# CAN-Bus_Shield.net
KiCad netlist of a schematic drawn in EAGLE
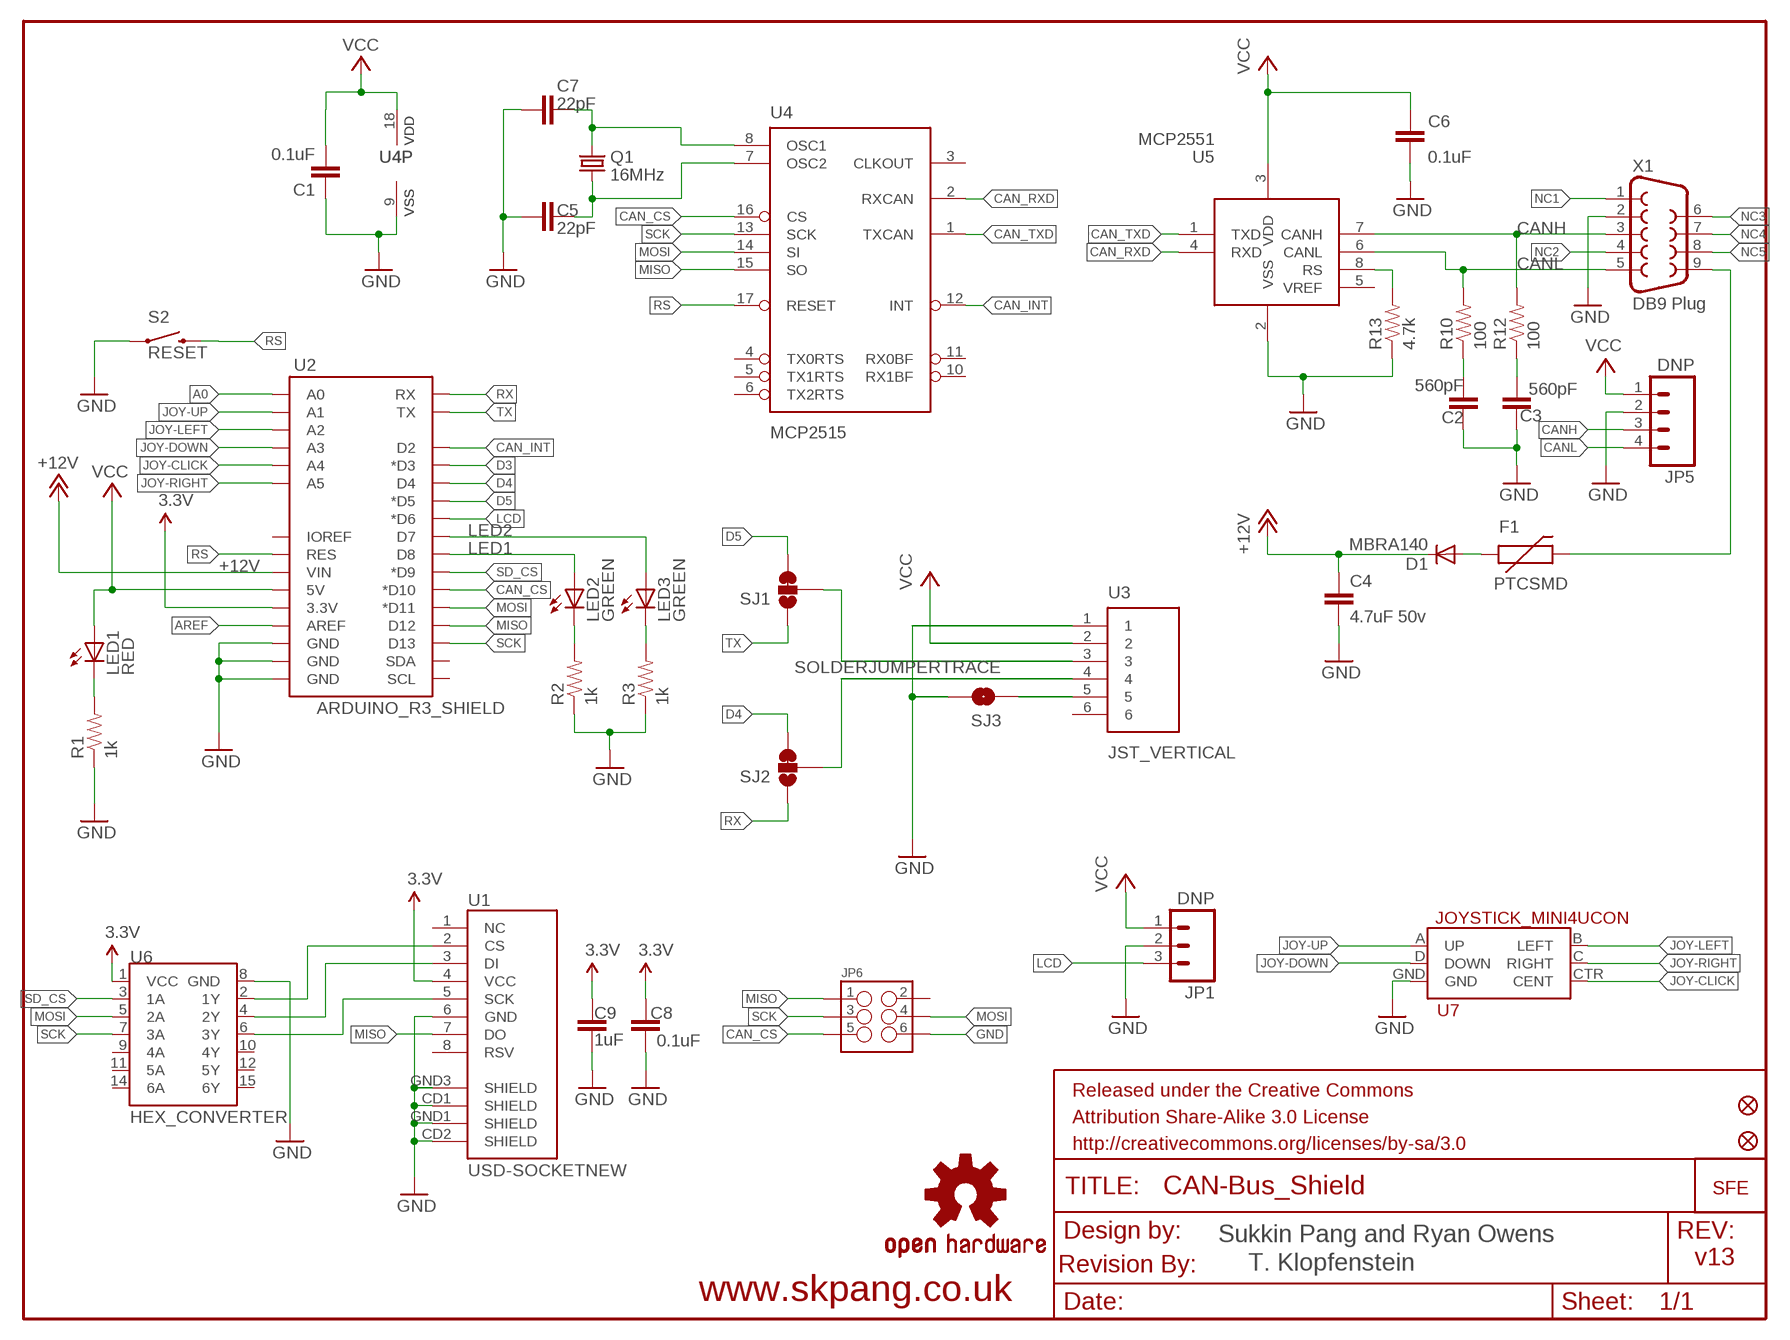
[diagram p0: schematic, sheet 1]

(export (version "E")
  (design (tool "Eeschema 10.0.6"))
  (components
    (comp (ref "C1")
      (value "0.1uF")
      (footprint "eagle-import:0603-CAP")
      (libsource (lib "eagle-import") (part "CAP0603-CAP"))
    )
    (comp (ref "C2")
      (value "560pF")
      (footprint "eagle-import:0603-CAP")
      (libsource (lib "eagle-import") (part "CAP0603-CAP"))
    )
    (comp (ref "C3")
      (value "560pF")
      (footprint "eagle-import:0603-CAP")
      (libsource (lib "eagle-import") (part "CAP0603-CAP"))
    )
    (comp (ref "C4")
      (value "4.7uF 50v")
      (footprint "eagle-import:0603-CAP")
      (libsource (lib "eagle-import") (part "CAP0603-CAP"))
    )
    (comp (ref "C5")
      (value "22pF")
      (footprint "eagle-import:0603-CAP")
      (libsource (lib "eagle-import") (part "CAP0603-CAP"))
    )
    (comp (ref "C6")
      (value "0.1uF")
      (footprint "eagle-import:0603-CAP")
      (libsource (lib "eagle-import") (part "CAP0603-CAP"))
    )
    (comp (ref "C7")
      (value "22pF")
      (footprint "eagle-import:0603-CAP")
      (libsource (lib "eagle-import") (part "CAP0603-CAP"))
    )
    (comp (ref "C8")
      (value "0.1uF")
      (footprint "eagle-import:0603-CAP")
      (libsource (lib "eagle-import") (part "CAP0603-CAP"))
    )
    (comp (ref "C9")
      (value "1uF")
      (footprint "eagle-import:0603-CAP")
      (libsource (lib "eagle-import") (part "CAP0603-CAP"))
    )
    (comp (ref "D1")
      (value "MBRA140")
      (footprint "eagle-import:SMA-DIODE")
      (libsource (lib "eagle-import") (part "DIODESMA"))
    )
    (comp (ref "F1")
      (value "PTCSMD")
      (footprint "eagle-import:PTC-1206")
      (libsource (lib "eagle-import") (part "PTCSMD"))
    )
    (comp (ref "FRAME1")
      (value "FRAME-LETTER")
      (footprint "eagle-import:CREATIVE_COMMONS")
      (libsource (lib "eagle-import") (part "FRAME-LETTER"))
    )
    (comp (ref "JP1")
      (value "DNP")
      (footprint "eagle-import:MOLEX-1X3_LOCK")
      (libsource (lib "eagle-import") (part "M03POLAR_LOCK"))
    )
    (comp (ref "JP2")
      (value "FIDUCIAL1X2")
      (footprint "eagle-import:FIDUCIAL-1X2")
      (libsource (lib "eagle-import") (part "FIDUCIAL1X2"))
    )
    (comp (ref "JP3")
      (value "FIDUCIAL1X2")
      (footprint "eagle-import:FIDUCIAL-1X2")
      (libsource (lib "eagle-import") (part "FIDUCIAL1X2"))
    )
    (comp (ref "JP4")
      (value "LOGO-SFENEW")
      (footprint "eagle-import:SFE-NEW-WEBLOGO")
      (libsource (lib "eagle-import") (part "LOGO-SFENEW"))
    )
    (comp (ref "JP5")
      (value "DNP")
      (footprint "eagle-import:1X04")
      (libsource (lib "eagle-import") (part "M04PTH"))
    )
    (comp (ref "JP6")
      (value "M03X2NO_SILK")
      (footprint "eagle-import:2X3-NS")
      (libsource (lib "eagle-import") (part "M03X2NO_SILK"))
    )
    (comp (ref "LED1")
      (value "RED")
      (footprint "eagle-import:LED-0603")
      (libsource (lib "eagle-import") (part "LED0603"))
    )
    (comp (ref "LED2")
      (value "GREEN")
      (footprint "eagle-import:LED-0603")
      (libsource (lib "eagle-import") (part "LED0603"))
    )
    (comp (ref "LED3")
      (value "GREEN")
      (footprint "eagle-import:LED-0603")
      (libsource (lib "eagle-import") (part "LED0603"))
    )
    (comp (ref "LOGO1")
      (value "OSHW-LOGOM")
      (footprint "eagle-import:OSHW-LOGO-M")
      (libsource (lib "eagle-import") (part "OSHW-LOGOM"))
    )
    (comp (ref "Q1")
      (value "16MHz")
      (footprint "eagle-import:CRYSTAL-SMD-5X3")
      (libsource (lib "eagle-import") (part "CRYSTAL5X3"))
    )
    (comp (ref "R1")
      (value "1k")
      (footprint "eagle-import:0603-RES")
      (libsource (lib "eagle-import") (part "RESISTOR0603-RES"))
    )
    (comp (ref "R2")
      (value "1k")
      (footprint "eagle-import:0603-RES")
      (libsource (lib "eagle-import") (part "RESISTOR0603-RES"))
    )
    (comp (ref "R3")
      (value "1k")
      (footprint "eagle-import:0603-RES")
      (libsource (lib "eagle-import") (part "RESISTOR0603-RES"))
    )
    (comp (ref "R10")
      (value "100")
      (footprint "eagle-import:0603-RES")
      (libsource (lib "eagle-import") (part "RESISTOR0603-RES"))
    )
    (comp (ref "R12")
      (value "100")
      (footprint "eagle-import:0603-RES")
      (libsource (lib "eagle-import") (part "RESISTOR0603-RES"))
    )
    (comp (ref "R13")
      (value "4.7k")
      (footprint "eagle-import:0603-RES")
      (libsource (lib "eagle-import") (part "RESISTOR0603-RES"))
    )
    (comp (ref "S2")
      (value "RESET")
      (footprint "eagle-import:TACTILE_SWITCH_SMD")
      (libsource (lib "eagle-import") (part "SWITCH-MOMENTARY-2SMD"))
    )
    (comp (ref "SJ1")
      (value "SOLDERJUMPER_2WAYPASTE2&3")
      (footprint "eagle-import:SJ_3_PASTE2&3")
      (libsource (lib "eagle-import") (part "SOLDERJUMPER_2WAYPASTE2&3"))
    )
    (comp (ref "SJ2")
      (value "SOLDERJUMPER_2WAYPASTE2&3")
      (footprint "eagle-import:SJ_3_PASTE2&3")
      (libsource (lib "eagle-import") (part "SOLDERJUMPER_2WAYPASTE2&3"))
    )
    (comp (ref "SJ3")
      (value "SOLDERJUMPERTRACE")
      (footprint "eagle-import:SJ_2S-TRACE")
      (libsource (lib "eagle-import") (part "SOLDERJUMPERTRACE"))
    )
    (comp (ref "U$1")
      (value "REVISION")
      (footprint "eagle-import:REVISION")
      (libsource (lib "eagle-import") (part "REVISION"))
    )
    (comp (ref "U1")
      (value "USD-SOCKETNEW")
      (footprint "eagle-import:MICRO-SD-SOCKET-PP")
      (libsource (lib "eagle-import") (part "USD-SOCKETNEW"))
    )
    (comp (ref "U2")
      (value "ARDUINO_R3_SHIELD")
      (footprint "eagle-import:UNO_R3_SHIELD")
      (libsource (lib "eagle-import") (part "ARDUINO_R3_SHIELD"))
    )
    (comp (ref "U3")
      (value "JST_VERTICAL")
      (footprint "eagle-import:JST-6-SMD-VERT-1.0MM")
      (libsource (lib "eagle-import") (part "JST_VERTICAL"))
    )
    (comp (ref "U4")
      (value "MCP2515")
      (footprint "eagle-import:SO-18W")
      (libsource (lib "eagle-import") (part "MCP2510SO"))
    )
    (comp (ref "U5")
      (value "MCP2551")
      (footprint "eagle-import:SO-08M")
      (libsource (lib "eagle-import") (part "MCP2551"))
    )
    (comp (ref "U6")
      (value "HEX_CONVERTER")
      (footprint "eagle-import:SO016")
      (libsource (lib "eagle-import") (part "HEX_CONVERTER"))
    )
    (comp (ref "U7")
      (value "JOYSTICK_MINI4UCON")
      (footprint "eagle-import:JOYSTICK_MINI")
      (libsource (lib "eagle-import") (part "JOYSTICK_MINI4UCON"))
    )
    (comp (ref "X1")
      (value "DB9 Plug")
      (footprint "eagle-import:DB9_MALE")
      (libsource (lib "eagle-import") (part "DB9MALE"))
    )
  )
  (nets
    (net (code "1") (name "+12V") (class "Default")
      (node (ref "C4") (pin "1") (pinfunction "1_1") (pintype "passive"))
      (node (ref "D1") (pin "C") (pinfunction "C_C") (pintype "passive"))
      (node (ref "U2") (pin "VIN") (pinfunction "VIN_VIN") (pintype "bidirectional"))
    )
    (net (code "2") (name "/LED1") (class "Default")
      (node (ref "LED2") (pin "A") (pinfunction "A_A") (pintype "passive"))
      (node (ref "U2") (pin "D8") (pinfunction "D8_D8") (pintype "bidirectional"))
    )
    (net (code "3") (name "/LED2") (class "Default")
      (node (ref "LED3") (pin "A") (pinfunction "A_A") (pintype "passive"))
      (node (ref "U2") (pin "D7") (pinfunction "D7_D7") (pintype "bidirectional"))
    )
    (net (code "4") (name "3.3V") (class "Default")
      (node (ref "C8") (pin "2") (pinfunction "2_2") (pintype "passive"))
      (node (ref "C9") (pin "1") (pinfunction "1_1") (pintype "passive"))
      (node (ref "U1") (pin "4") (pinfunction "VCC_4") (pintype "bidirectional"))
      (node (ref "U2") (pin "3.3V") (pinfunction "3.3V_3.3V") (pintype "bidirectional"))
      (node (ref "U6") (pin "1") (pinfunction "VCC_1") (pintype "bidirectional"))
    )
    (net (code "5") (name "A0") (class "Default")
      (node (ref "U2") (pin "A0") (pinfunction "A0_A0") (pintype "bidirectional"))
    )
    (net (code "6") (name "AREF") (class "Default")
      (node (ref "U2") (pin "AREF") (pinfunction "AREF_AREF") (pintype "bidirectional"))
    )
    (net (code "7") (name "CANH") (class "Default")
      (node (ref "JP5") (pin "3") (pinfunction "3_3") (pintype "passive"))
      (node (ref "R12") (pin "2") (pinfunction "2_2") (pintype "passive"))
      (node (ref "U5") (pin "7") (pinfunction "CANH_7") (pintype "bidirectional"))
      (node (ref "X1") (pin "3") (pinfunction "3_3") (pintype "passive"))
    )
    (net (code "8") (name "CANL") (class "Default")
      (node (ref "JP5") (pin "4") (pinfunction "4_4") (pintype "passive"))
      (node (ref "R10") (pin "2") (pinfunction "2_2") (pintype "passive"))
      (node (ref "U5") (pin "6") (pinfunction "CANL_6") (pintype "bidirectional"))
      (node (ref "X1") (pin "5") (pinfunction "5_5") (pintype "passive"))
    )
    (net (code "9") (name "CAN_CS") (class "Default")
      (node (ref "JP6") (pin "5") (pinfunction "5_5") (pintype "bidirectional"))
      (node (ref "U2") (pin "D10") (pinfunction "*D10_D10") (pintype "bidirectional"))
      (node (ref "U4") (pin "16") (pinfunction "CS_16") (pintype "input"))
    )
    (net (code "10") (name "CAN_INT") (class "Default")
      (node (ref "U2") (pin "D2") (pinfunction "D2_D2") (pintype "bidirectional"))
      (node (ref "U4") (pin "12") (pinfunction "INT_12") (pintype "output"))
    )
    (net (code "11") (name "CAN_RXD") (class "Default")
      (node (ref "U4") (pin "2") (pinfunction "RXCAN_2") (pintype "input"))
      (node (ref "U5") (pin "4") (pinfunction "RXD_4") (pintype "bidirectional"))
    )
    (net (code "12") (name "CAN_TXD") (class "Default")
      (node (ref "U4") (pin "1") (pinfunction "TXCAN_1") (pintype "output"))
      (node (ref "U5") (pin "1") (pinfunction "TXD_1") (pintype "bidirectional"))
    )
    (net (code "13") (name "D3") (class "Default")
      (node (ref "U2") (pin "D3") (pinfunction "*D3_D3") (pintype "bidirectional"))
    )
    (net (code "14") (name "D4") (class "Default")
      (node (ref "SJ2") (pin "3") (pinfunction "3_3") (pintype "passive"))
      (node (ref "U2") (pin "D4") (pinfunction "D4_D4") (pintype "bidirectional"))
    )
    (net (code "15") (name "D5") (class "Default")
      (node (ref "SJ1") (pin "3") (pinfunction "3_3") (pintype "passive"))
      (node (ref "U2") (pin "D5") (pinfunction "*D5_D5") (pintype "bidirectional"))
    )
    (net (code "16") (name "GND") (class "Default")
      (node (ref "C1") (pin "1") (pinfunction "1_1") (pintype "passive"))
      (node (ref "C2") (pin "1") (pinfunction "1_1") (pintype "passive"))
      (node (ref "C3") (pin "1") (pinfunction "1_1") (pintype "passive"))
      (node (ref "C4") (pin "2") (pinfunction "2_2") (pintype "passive"))
      (node (ref "C5") (pin "1") (pinfunction "1_1") (pintype "passive"))
      (node (ref "C6") (pin "1") (pinfunction "1_1") (pintype "passive"))
      (node (ref "C7") (pin "1") (pinfunction "1_1") (pintype "passive"))
      (node (ref "C8") (pin "1") (pinfunction "1_1") (pintype "passive"))
      (node (ref "C9") (pin "2") (pinfunction "2_2") (pintype "passive"))
      (node (ref "JP1") (pin "2") (pinfunction "2_2") (pintype "passive"))
      (node (ref "JP5") (pin "2") (pinfunction "2_2") (pintype "passive"))
      (node (ref "JP6") (pin "6") (pinfunction "6_6") (pintype "bidirectional"))
      (node (ref "R1") (pin "1") (pinfunction "1_1") (pintype "passive"))
      (node (ref "R13") (pin "1") (pinfunction "1_1") (pintype "passive"))
      (node (ref "R2") (pin "1") (pinfunction "1_1") (pintype "passive"))
      (node (ref "R3") (pin "1") (pinfunction "1_1") (pintype "passive"))
      (node (ref "S2") (pin "1") (pinfunction "1_1") (pintype "passive"))
      (node (ref "SJ3") (pin "2") (pinfunction "2_2") (pintype "passive"))
      (node (ref "U1") (pin "6") (pinfunction "GND_6") (pintype "bidirectional"))
      (node (ref "U1") (pin "CD1") (pinfunction "SHIELD_CD1") (pintype "bidirectional"))
      (node (ref "U1") (pin "CD2") (pinfunction "SHIELD_CD2") (pintype "bidirectional"))
      (node (ref "U1") (pin "GND1") (pinfunction "SHIELD_GND1") (pintype "bidirectional"))
      (node (ref "U1") (pin "GND3") (pinfunction "SHIELD_GND3") (pintype "bidirectional"))
      (node (ref "U2") (pin "GND@0") (pinfunction "GND_GND@0") (pintype "bidirectional"))
      (node (ref "U2") (pin "GND@1") (pinfunction "GND_GND@1") (pintype "bidirectional"))
      (node (ref "U2") (pin "GND@2") (pinfunction "GND_GND@2") (pintype "bidirectional"))
      (node (ref "U3") (pin "1") (pinfunction "1_1") (pintype "bidirectional"))
      (node (ref "U4") (pin "9") (pinfunction "VSS_9") (pintype "power_in"))
      (node (ref "U5") (pin "2") (pinfunction "VSS_2") (pintype "power_in"))
      (node (ref "U6") (pin "8") (pinfunction "GND_8") (pintype "bidirectional"))
      (node (ref "U7") (pin "GND") (pinfunction "GND_GND") (pintype "bidirectional"))
      (node (ref "X1") (pin "2") (pinfunction "2_2") (pintype "passive"))
    )
    (net (code "17") (name "JOY-CLICK") (class "Default")
      (node (ref "U2") (pin "A4") (pinfunction "A4_A4") (pintype "bidirectional"))
      (node (ref "U7") (pin "CTR") (pinfunction "CENT_CTR") (pintype "bidirectional"))
    )
    (net (code "18") (name "JOY-DOWN") (class "Default")
      (node (ref "U2") (pin "A3") (pinfunction "A3_A3") (pintype "bidirectional"))
      (node (ref "U7") (pin "D") (pinfunction "DOWN_D") (pintype "bidirectional"))
    )
    (net (code "19") (name "JOY-LEFT") (class "Default")
      (node (ref "U2") (pin "A2") (pinfunction "A2_A2") (pintype "bidirectional"))
      (node (ref "U7") (pin "B") (pinfunction "LEFT_B") (pintype "bidirectional"))
    )
    (net (code "20") (name "JOY-RIGHT") (class "Default")
      (node (ref "U2") (pin "A5") (pinfunction "A5_A5") (pintype "bidirectional"))
      (node (ref "U7") (pin "C") (pinfunction "RIGHT_C") (pintype "bidirectional"))
    )
    (net (code "21") (name "JOY-UP") (class "Default")
      (node (ref "U2") (pin "A1") (pinfunction "A1_A1") (pintype "bidirectional"))
      (node (ref "U7") (pin "A") (pinfunction "UP_A") (pintype "bidirectional"))
    )
    (net (code "22") (name "LCD") (class "Default")
      (node (ref "JP1") (pin "3") (pinfunction "3_3") (pintype "passive"))
      (node (ref "U2") (pin "D6") (pinfunction "*D6_D6") (pintype "bidirectional"))
    )
    (net (code "23") (name "MISO") (class "Default")
      (node (ref "JP6") (pin "1") (pinfunction "1_1") (pintype "bidirectional"))
      (node (ref "U1") (pin "7") (pinfunction "DO_7") (pintype "bidirectional"))
      (node (ref "U2") (pin "D12") (pinfunction "D12_D12") (pintype "bidirectional"))
      (node (ref "U4") (pin "15") (pinfunction "SO_15") (pintype "output"))
    )
    (net (code "24") (name "MOSI") (class "Default")
      (node (ref "JP6") (pin "4") (pinfunction "4_4") (pintype "bidirectional"))
      (node (ref "U2") (pin "D11") (pinfunction "*D11_D11") (pintype "bidirectional"))
      (node (ref "U4") (pin "14") (pinfunction "SI_14") (pintype "input"))
      (node (ref "U6") (pin "5") (pinfunction "2A_5") (pintype "bidirectional"))
    )
    (net (code "25") (name "NC1") (class "Default")
      (node (ref "X1") (pin "1") (pinfunction "1_1") (pintype "passive"))
    )
    (net (code "26") (name "NC2") (class "Default")
      (node (ref "X1") (pin "4") (pinfunction "4_4") (pintype "passive"))
    )
    (net (code "27") (name "NC3") (class "Default")
      (node (ref "X1") (pin "6") (pinfunction "6_6") (pintype "passive"))
    )
    (net (code "28") (name "NC4") (class "Default")
      (node (ref "X1") (pin "7") (pinfunction "7_7") (pintype "passive"))
    )
    (net (code "29") (name "NC5") (class "Default")
      (node (ref "X1") (pin "8") (pinfunction "8_8") (pintype "passive"))
    )
    (net (code "30") (name "Net-(C2-Pad2)") (class "Default")
      (node (ref "C2") (pin "2") (pinfunction "2_2") (pintype "passive"))
      (node (ref "R10") (pin "1") (pinfunction "1_1") (pintype "passive"))
    )
    (net (code "31") (name "Net-(C3-Pad2)") (class "Default")
      (node (ref "C3") (pin "2") (pinfunction "2_2") (pintype "passive"))
      (node (ref "R12") (pin "1") (pinfunction "1_1") (pintype "passive"))
    )
    (net (code "32") (name "Net-(D1-PadA)") (class "Default")
      (node (ref "D1") (pin "A") (pinfunction "A_A") (pintype "passive"))
      (node (ref "F1") (pin "1") (pinfunction "1_1") (pintype "bidirectional"))
    )
    (net (code "33") (name "Net-(F1-Pad2)") (class "Default")
      (node (ref "F1") (pin "2") (pinfunction "2_2") (pintype "bidirectional"))
      (node (ref "X1") (pin "9") (pinfunction "9_9") (pintype "passive"))
    )
    (net (code "34") (name "Net-(LED1-PadC)") (class "Default")
      (node (ref "LED1") (pin "C") (pinfunction "C_C") (pintype "passive"))
      (node (ref "R1") (pin "2") (pinfunction "2_2") (pintype "passive"))
    )
    (net (code "35") (name "Net-(LED2-PadC)") (class "Default")
      (node (ref "LED2") (pin "C") (pinfunction "C_C") (pintype "passive"))
      (node (ref "R2") (pin "2") (pinfunction "2_2") (pintype "passive"))
    )
    (net (code "36") (name "Net-(LED3-PadC)") (class "Default")
      (node (ref "LED3") (pin "C") (pinfunction "C_C") (pintype "passive"))
      (node (ref "R3") (pin "2") (pinfunction "2_2") (pintype "passive"))
    )
    (net (code "37") (name "Net-(Q1-2)") (class "Default")
      (node (ref "C7") (pin "2") (pinfunction "2_2") (pintype "passive"))
      (node (ref "Q1") (pin "3") (pinfunction "2_3") (pintype "passive"))
      (node (ref "U4") (pin "8") (pinfunction "OSC1_8") (pintype "input"))
    )
    (net (code "38") (name "Net-(SJ1-Pad2)") (class "Default")
      (node (ref "SJ1") (pin "2") (pinfunction "2_2") (pintype "passive"))
      (node (ref "U3") (pin "3") (pinfunction "3_3") (pintype "bidirectional"))
    )
    (net (code "39") (name "Net-(SJ2-Pad2)") (class "Default")
      (node (ref "SJ2") (pin "2") (pinfunction "2_2") (pintype "passive"))
      (node (ref "U3") (pin "4") (pinfunction "4_4") (pintype "bidirectional"))
    )
    (net (code "40") (name "Net-(SJ3-Pad1)") (class "Default")
      (node (ref "SJ3") (pin "1") (pinfunction "1_1") (pintype "passive"))
      (node (ref "U3") (pin "5") (pinfunction "5_5") (pintype "bidirectional"))
    )
    (net (code "41") (name "Net-(U1-CS)") (class "Default")
      (node (ref "U1") (pin "2") (pinfunction "CS_2") (pintype "bidirectional"))
      (node (ref "U6") (pin "2") (pinfunction "1Y_2") (pintype "bidirectional"))
    )
    (net (code "42") (name "Net-(U1-DI)") (class "Default")
      (node (ref "U1") (pin "3") (pinfunction "DI_3") (pintype "bidirectional"))
      (node (ref "U6") (pin "4") (pinfunction "2Y_4") (pintype "bidirectional"))
    )
    (net (code "43") (name "Net-(U1-SCK)") (class "Default")
      (node (ref "U1") (pin "5") (pinfunction "SCK_5") (pintype "bidirectional"))
      (node (ref "U6") (pin "6") (pinfunction "3Y_6") (pintype "bidirectional"))
    )
    (net (code "44") (name "Net-(U4A-OSC2)") (class "Default")
      (node (ref "C5") (pin "2") (pinfunction "2_2") (pintype "passive"))
      (node (ref "Q1") (pin "1") (pinfunction "1_1") (pintype "passive"))
      (node (ref "U4") (pin "7") (pinfunction "OSC2_7") (pintype "output"))
    )
    (net (code "45") (name "Net-(U5-RS)") (class "Default")
      (node (ref "R13") (pin "2") (pinfunction "2_2") (pintype "passive"))
      (node (ref "U5") (pin "8") (pinfunction "RS_8") (pintype "bidirectional"))
    )
    (net (code "46") (name "RS") (class "Default")
      (node (ref "S2") (pin "3") (pinfunction "2_3") (pintype "passive"))
      (node (ref "U2") (pin "RES") (pinfunction "RES_RES") (pintype "bidirectional"))
      (node (ref "U4") (pin "17") (pinfunction "RESET_17") (pintype "input"))
    )
    (net (code "47") (name "RX") (class "Default")
      (node (ref "SJ2") (pin "1") (pinfunction "1_1") (pintype "passive"))
      (node (ref "U2") (pin "RX") (pinfunction "RX_RX") (pintype "bidirectional"))
    )
    (net (code "48") (name "SCK") (class "Default")
      (node (ref "JP6") (pin "3") (pinfunction "3_3") (pintype "bidirectional"))
      (node (ref "U2") (pin "D13") (pinfunction "D13_D13") (pintype "bidirectional"))
      (node (ref "U4") (pin "13") (pinfunction "SCK_13") (pintype "input"))
      (node (ref "U6") (pin "7") (pinfunction "3A_7") (pintype "bidirectional"))
    )
    (net (code "49") (name "SD_CS") (class "Default")
      (node (ref "U2") (pin "D9") (pinfunction "*D9_D9") (pintype "bidirectional"))
      (node (ref "U6") (pin "3") (pinfunction "1A_3") (pintype "bidirectional"))
    )
    (net (code "50") (name "TX") (class "Default")
      (node (ref "SJ1") (pin "1") (pinfunction "1_1") (pintype "passive"))
      (node (ref "U2") (pin "TX") (pinfunction "TX_TX") (pintype "bidirectional"))
    )
    (net (code "51") (name "VCC") (class "Default")
      (node (ref "C1") (pin "2") (pinfunction "2_2") (pintype "passive"))
      (node (ref "C6") (pin "2") (pinfunction "2_2") (pintype "passive"))
      (node (ref "JP1") (pin "1") (pinfunction "1_1") (pintype "passive"))
      (node (ref "JP5") (pin "1") (pinfunction "1_1") (pintype "passive"))
      (node (ref "LED1") (pin "A") (pinfunction "A_A") (pintype "passive"))
      (node (ref "U2") (pin "5V") (pinfunction "5V_5V") (pintype "bidirectional"))
      (node (ref "U3") (pin "2") (pinfunction "2_2") (pintype "bidirectional"))
      (node (ref "U4") (pin "18") (pinfunction "VDD_18") (pintype "power_in"))
      (node (ref "U5") (pin "3") (pinfunction "VDD_3") (pintype "power_in"))
    )
    (net (code "52") (name "unconnected-(JP6-Pad2)") (class "Default")
      (node (ref "JP6") (pin "2") (pinfunction "2_2") (pintype "bidirectional"))
    )
    (net (code "53") (name "unconnected-(U1-NC-Pad1)") (class "Default")
      (node (ref "U1") (pin "1") (pinfunction "NC_1") (pintype "bidirectional"))
    )
    (net (code "54") (name "unconnected-(U1-RSV-Pad8)") (class "Default")
      (node (ref "U1") (pin "8") (pinfunction "RSV_8") (pintype "bidirectional"))
    )
    (net (code "55") (name "unconnected-(U2-PadIOREF)") (class "Default")
      (node (ref "U2") (pin "IOREF") (pinfunction "IOREF_IOREF") (pintype "bidirectional"))
    )
    (net (code "56") (name "unconnected-(U2-PadSCL)") (class "Default")
      (node (ref "U2") (pin "SCL") (pinfunction "SCL_SCL") (pintype "bidirectional"))
    )
    (net (code "57") (name "unconnected-(U2-PadSDA)") (class "Default")
      (node (ref "U2") (pin "SDA") (pinfunction "SDA_SDA") (pintype "bidirectional"))
    )
    (net (code "58") (name "unconnected-(U3-Pad6)") (class "Default")
      (node (ref "U3") (pin "6") (pinfunction "6_6") (pintype "bidirectional"))
    )
    (net (code "59") (name "unconnected-(U4A-CLKOUT-Pad3)") (class "Default")
      (node (ref "U4") (pin "3") (pinfunction "CLKOUT_3") (pintype "output"))
    )
    (net (code "60") (name "unconnected-(U4A-RX0BF-Pad11)") (class "Default")
      (node (ref "U4") (pin "11") (pinfunction "RX0BF_11") (pintype "output"))
    )
    (net (code "61") (name "unconnected-(U4A-RX1BF-Pad10)") (class "Default")
      (node (ref "U4") (pin "10") (pinfunction "RX1BF_10") (pintype "output"))
    )
    (net (code "62") (name "unconnected-(U4A-TX0RTS-Pad4)") (class "Default")
      (node (ref "U4") (pin "4") (pinfunction "TX0RTS_4") (pintype "input"))
    )
    (net (code "63") (name "unconnected-(U4A-TX1RTS-Pad5)") (class "Default")
      (node (ref "U4") (pin "5") (pinfunction "TX1RTS_5") (pintype "input"))
    )
    (net (code "64") (name "unconnected-(U4A-TX2RTS-Pad6)") (class "Default")
      (node (ref "U4") (pin "6") (pinfunction "TX2RTS_6") (pintype "input"))
    )
    (net (code "65") (name "unconnected-(U5-VREF-Pad5)") (class "Default")
      (node (ref "U5") (pin "5") (pinfunction "VREF_5") (pintype "bidirectional"))
    )
    (net (code "66") (name "unconnected-(U6-4A-Pad9)") (class "Default")
      (node (ref "U6") (pin "9") (pinfunction "4A_9") (pintype "bidirectional"))
    )
    (net (code "67") (name "unconnected-(U6-4Y-Pad10)") (class "Default")
      (node (ref "U6") (pin "10") (pinfunction "4Y_10") (pintype "bidirectional"))
    )
    (net (code "68") (name "unconnected-(U6-5A-Pad11)") (class "Default")
      (node (ref "U6") (pin "11") (pinfunction "5A_11") (pintype "bidirectional"))
    )
    (net (code "69") (name "unconnected-(U6-5Y-Pad12)") (class "Default")
      (node (ref "U6") (pin "12") (pinfunction "5Y_12") (pintype "bidirectional"))
    )
    (net (code "70") (name "unconnected-(U6-6A-Pad14)") (class "Default")
      (node (ref "U6") (pin "14") (pinfunction "6A_14") (pintype "bidirectional"))
    )
    (net (code "71") (name "unconnected-(U6-6Y-Pad15)") (class "Default")
      (node (ref "U6") (pin "15") (pinfunction "6Y_15") (pintype "bidirectional"))
    )
  )
)
